# 03_MCU.net
KiCad netlist of a schematic drawn in Altium Designer
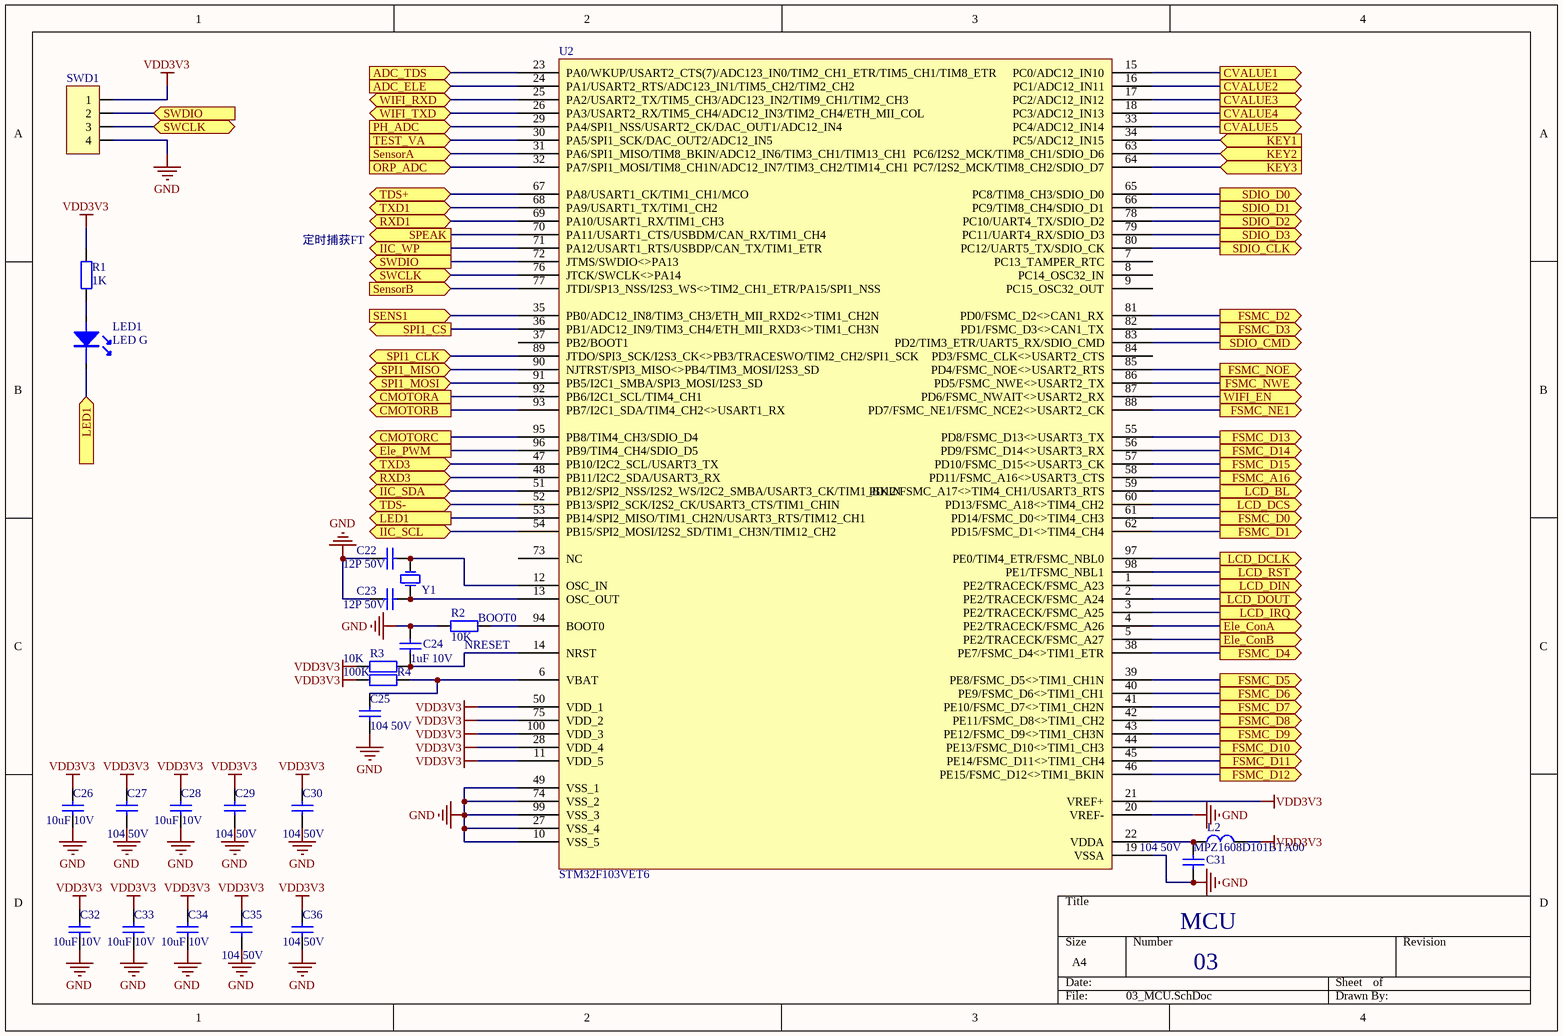
[diagram p0: 03_MCU.SchDoc]

(export (version "E")
  (design (tool "Eeschema 10.0.6"))
  (components
    (comp (ref "C22")
      (value "12P 50V")
      (footprint "SMD-0603C")
      (description "贴片电容 5%")
      (libsource (lib "XiaoyI") (part "CAP4"))
    )
    (comp (ref "C23")
      (value "12P 50V")
      (footprint "SMD-0603C")
      (description "贴片电容 5%")
      (libsource (lib "XiaoyI") (part "CAP4"))
    )
    (comp (ref "C24")
      (value "1uF 10V")
      (footprint "SMD-0603C")
      (description "贴片电容 20%")
      (libsource (lib "XiaoyI") (part "CAP4"))
    )
    (comp (ref "C25")
      (value "104 50V")
      (footprint "SMD-0603C")
      (description "贴片电容 20%")
      (libsource (lib "XiaoyI") (part "CAP4"))
    )
    (comp (ref "C26")
      (value "10uF 10V")
      (footprint "SMD-0603C")
      (description "贴片电容 20%")
      (libsource (lib "XiaoyI") (part "CAP4"))
    )
    (comp (ref "C27")
      (value "104 50V")
      (footprint "SMD-0603C")
      (description "贴片电容 20%")
      (libsource (lib "XiaoyI") (part "CAP4"))
    )
    (comp (ref "C28")
      (value "10uF 10V")
      (footprint "SMD-0603C")
      (description "贴片电容 20%")
      (libsource (lib "XiaoyI") (part "CAP4"))
    )
    (comp (ref "C29")
      (value "104 50V")
      (footprint "SMD-0603C")
      (description "贴片电容 20%")
      (libsource (lib "XiaoyI") (part "CAP4"))
    )
    (comp (ref "C30")
      (value "104 50V")
      (footprint "SMD-0603C")
      (description "贴片电容 20%")
      (libsource (lib "XiaoyI") (part "CAP4"))
    )
    (comp (ref "C31")
      (value "104 50V")
      (footprint "SMD-0603C")
      (description "贴片电容 20%")
      (libsource (lib "XiaoyI") (part "CAP4"))
    )
    (comp (ref "C32")
      (value "10uF 10V")
      (footprint "SMD-0603C")
      (description "贴片电容 20%")
      (libsource (lib "XiaoyI") (part "CAP4"))
    )
    (comp (ref "C33")
      (value "10uF 10V")
      (footprint "SMD-0603C")
      (description "贴片电容 20%")
      (libsource (lib "XiaoyI") (part "CAP4"))
    )
    (comp (ref "C34")
      (value "10uF 10V")
      (footprint "SMD-0603C")
      (description "贴片电容 20%")
      (libsource (lib "XiaoyI") (part "CAP4"))
    )
    (comp (ref "C35")
      (value "104 50V")
      (footprint "SMD-0603C")
      (description "贴片电容 20%")
      (libsource (lib "XiaoyI") (part "CAP4"))
    )
    (comp (ref "C36")
      (value "104 50V")
      (footprint "SMD-0603C")
      (description "贴片电容 20%")
      (libsource (lib "XiaoyI") (part "CAP4"))
    )
    (comp (ref "L2")
      (value "MPZ1608D101BTA00")
      (footprint "SMD-0603")
      (description "磁珠电感 100R 100MHz")
      (libsource (lib "XiaoyI") (part "CIZHU1"))
    )
    (comp (ref "LED1")
      (value "LED G")
      (footprint "SMD-0603D")
      (description "绿色普亮")
      (libsource (lib "ABB") (part "LED"))
    )
    (comp (ref "R1")
      (value "1K")
      (footprint "SMD-0603")
      (description "贴片电阻 5%")
      (libsource (lib "ABB") (part "RES0"))
    )
    (comp (ref "R2")
      (value "10K")
      (footprint "SMD-0603")
      (description "贴片电阻 5%")
      (libsource (lib "XiaoyI") (part "RES2"))
    )
    (comp (ref "R3")
      (value "10K")
      (footprint "SMD-0603")
      (description "贴片电阻 5%")
      (libsource (lib "XiaoyI") (part "RES2"))
    )
    (comp (ref "R4")
      (value "100K")
      (footprint "SMD-0603")
      (description "贴片电阻 5%")
      (libsource (lib "XiaoyI") (part "RES2"))
    )
    (comp (ref "SWD1")
      (value "SIP-4 (NC)")
      (footprint "SIP-4")
      (description "ISP 下载")
      (libsource (lib "XiaoyI") (part "SIP-4"))
    )
    (comp (ref "U2")
      (value "STM32F103VET6")
      (footprint "LQFP-100_14X14X05P")
      (libsource (lib "liujingtao_V1.0") (part "STM32F103VET6"))
    )
    (comp (ref "Y1")
      (value "8MHz")
      (footprint "XTAL-3225-2")
      (description "3225 贴片晶振")
      (libsource (lib "XiaoyI") (part "XTAL"))
    )
  )
  (nets
    (net (code "1") (name "/ADC_ELE") (class "Default")
      (node (ref "U2") (pin "24") (pinfunction "PA1/USART2_RTS/ADC123_IN1/TIM5_CH2/TIM2_CH2_24") (pintype "passive"))
    )
    (net (code "2") (name "/ADC_TDS") (class "Default")
      (node (ref "U2") (pin "23") (pinfunction "PA0/WKUP/USART2_CTS(7)/ADC123_IN0/TIM2_CH1_ETR/TIM5_CH1/TIM8_ETR_23") (pintype "passive"))
    )
    (net (code "3") (name "/CMOTORA") (class "Default")
      (node (ref "U2") (pin "92") (pinfunction "PB6/I2C1_SCL/TIM4_CH1_92") (pintype "passive"))
    )
    (net (code "4") (name "/CMOTORB") (class "Default")
      (node (ref "U2") (pin "93") (pinfunction "PB7/I2C1_SDA/TIM4_CH2<>USART1_RX_93") (pintype "passive"))
    )
    (net (code "5") (name "/CMOTORC") (class "Default")
      (node (ref "U2") (pin "95") (pinfunction "PB8/TIM4_CH3/SDIO_D4_95") (pintype "passive"))
    )
    (net (code "6") (name "/CVALUE1") (class "Default")
      (node (ref "U2") (pin "15") (pinfunction "PC0/ADC12_IN10_15") (pintype "passive"))
    )
    (net (code "7") (name "/CVALUE2") (class "Default")
      (node (ref "U2") (pin "16") (pinfunction "PC1/ADC12_IN11_16") (pintype "passive"))
    )
    (net (code "8") (name "/CVALUE3") (class "Default")
      (node (ref "U2") (pin "17") (pinfunction "PC2/ADC12_IN12_17") (pintype "passive"))
    )
    (net (code "9") (name "/CVALUE4") (class "Default")
      (node (ref "U2") (pin "18") (pinfunction "PC3/ADC12_IN13_18") (pintype "passive"))
    )
    (net (code "10") (name "/CVALUE5") (class "Default")
      (node (ref "U2") (pin "33") (pinfunction "PC4/ADC12_IN14_33") (pintype "passive"))
    )
    (net (code "11") (name "/Ele_ConA") (class "Default")
      (node (ref "U2") (pin "4") (pinfunction "PE2/TRACECK/FSMC_A26_4") (pintype "passive"))
    )
    (net (code "12") (name "/Ele_ConB") (class "Default")
      (node (ref "U2") (pin "5") (pinfunction "PE2/TRACECK/FSMC_A27_5") (pintype "passive"))
    )
    (net (code "13") (name "/Ele_PWM") (class "Default")
      (node (ref "U2") (pin "96") (pinfunction "PB9/TIM4_CH4/SDIO_D5_96") (pintype "passive"))
    )
    (net (code "14") (name "/FSMC_A16") (class "Default")
      (node (ref "U2") (pin "58") (pinfunction "PD11/FSMC_A16<>USART3_CTS_58") (pintype "passive"))
    )
    (net (code "15") (name "/FSMC_D0") (class "Default")
      (node (ref "U2") (pin "61") (pinfunction "PD14/FSMC_D0<>TIM4_CH3_61") (pintype "passive"))
    )
    (net (code "16") (name "/FSMC_D1") (class "Default")
      (node (ref "U2") (pin "62") (pinfunction "PD15/FSMC_D1<>TIM4_CH4_62") (pintype "passive"))
    )
    (net (code "17") (name "/FSMC_D2") (class "Default")
      (node (ref "U2") (pin "81") (pinfunction "PD0/FSMC_D2<>CAN1_RX_81") (pintype "passive"))
    )
    (net (code "18") (name "/FSMC_D3") (class "Default")
      (node (ref "U2") (pin "82") (pinfunction "PD1/FSMC_D3<>CAN1_TX_82") (pintype "passive"))
    )
    (net (code "19") (name "/FSMC_D4") (class "Default")
      (node (ref "U2") (pin "38") (pinfunction "PE7/FSMC_D4<>TIM1_ETR_38") (pintype "passive"))
    )
    (net (code "20") (name "/FSMC_D5") (class "Default")
      (node (ref "U2") (pin "39") (pinfunction "PE8/FSMC_D5<>TIM1_CH1N_39") (pintype "passive"))
    )
    (net (code "21") (name "/FSMC_D6") (class "Default")
      (node (ref "U2") (pin "40") (pinfunction "PE9/FSMC_D6<>TIM1_CH1_40") (pintype "passive"))
    )
    (net (code "22") (name "/FSMC_D7") (class "Default")
      (node (ref "U2") (pin "41") (pinfunction "PE10/FSMC_D7<>TIM1_CH2N_41") (pintype "passive"))
    )
    (net (code "23") (name "/FSMC_D8") (class "Default")
      (node (ref "U2") (pin "42") (pinfunction "PE11/FSMC_D8<>TIM1_CH2_42") (pintype "passive"))
    )
    (net (code "24") (name "/FSMC_D9") (class "Default")
      (node (ref "U2") (pin "43") (pinfunction "PE12/FSMC_D9<>TIM1_CH3N_43") (pintype "passive"))
    )
    (net (code "25") (name "/FSMC_D10") (class "Default")
      (node (ref "U2") (pin "44") (pinfunction "PE13/FSMC_D10<>TIM1_CH3_44") (pintype "passive"))
    )
    (net (code "26") (name "/FSMC_D11") (class "Default")
      (node (ref "U2") (pin "45") (pinfunction "PE14/FSMC_D11<>TIM1_CH4_45") (pintype "passive"))
    )
    (net (code "27") (name "/FSMC_D12") (class "Default")
      (node (ref "U2") (pin "46") (pinfunction "PE15/FSMC_D12<>TIM1_BKIN_46") (pintype "passive"))
    )
    (net (code "28") (name "/FSMC_D13") (class "Default")
      (node (ref "U2") (pin "55") (pinfunction "PD8/FSMC_D13<>USART3_TX_55") (pintype "passive"))
    )
    (net (code "29") (name "/FSMC_D14") (class "Default")
      (node (ref "U2") (pin "56") (pinfunction "PD9/FSMC_D14<>USART3_RX_56") (pintype "passive"))
    )
    (net (code "30") (name "/FSMC_D15") (class "Default")
      (node (ref "U2") (pin "57") (pinfunction "PD10/FSMC_D15<>USART3_CK_57") (pintype "passive"))
    )
    (net (code "31") (name "/FSMC_NE1") (class "Default")
      (node (ref "U2") (pin "88") (pinfunction "PD7/FSMC_NE1/FSMC_NCE2<>USART2_CK_88") (pintype "passive"))
    )
    (net (code "32") (name "/FSMC_NOE") (class "Default")
      (node (ref "U2") (pin "85") (pinfunction "PD4/FSMC_NOE<>USART2_RTS_85") (pintype "passive"))
    )
    (net (code "33") (name "/FSMC_NWE") (class "Default")
      (node (ref "U2") (pin "86") (pinfunction "PD5/FSMC_NWE<>USART2_TX_86") (pintype "passive"))
    )
    (net (code "34") (name "/IIC_SCL") (class "Default")
      (node (ref "U2") (pin "54") (pinfunction "PB15/SPI2_MOSI/I2S2_SD/TIM1_CH3N/TIM12_CH2_54") (pintype "passive"))
    )
    (net (code "35") (name "/IIC_SDA") (class "Default")
      (node (ref "U2") (pin "51") (pinfunction "PB12/SPI2_NSS/I2S2_WS/I2C2_SMBA/USART3_CK/TIM1_BKIN_51") (pintype "passive"))
    )
    (net (code "36") (name "/IIC_WP") (class "Default")
      (node (ref "U2") (pin "71") (pinfunction "PA12/USART1_RTS/USBDP/CAN_TX/TIM1_ETR_71") (pintype "passive"))
    )
    (net (code "37") (name "/KEY1") (class "Default")
      (node (ref "U2") (pin "34") (pinfunction "PC5/ADC12_IN15_34") (pintype "passive"))
    )
    (net (code "38") (name "/KEY2") (class "Default")
      (node (ref "U2") (pin "63") (pinfunction "PC6/I2S2_MCK/TIM8_CH1/SDIO_D6_63") (pintype "passive"))
    )
    (net (code "39") (name "/KEY3") (class "Default")
      (node (ref "U2") (pin "64") (pinfunction "PC7/I2S2_MCK/TIM8_CH2/SDIO_D7_64") (pintype "passive"))
    )
    (net (code "40") (name "/LCD_BL") (class "Default")
      (node (ref "U2") (pin "59") (pinfunction "PD12/FSMC_A17<>TIM4_CH1/USART3_RTS_59") (pintype "passive"))
    )
    (net (code "41") (name "/LCD_DCLK") (class "Default")
      (node (ref "U2") (pin "97") (pinfunction "PE0/TIM4_ETR/FSMC_NBL0_97") (pintype "passive"))
    )
    (net (code "42") (name "/LCD_DCS") (class "Default")
      (node (ref "U2") (pin "60") (pinfunction "PD13/FSMC_A18<>TIM4_CH2_60") (pintype "passive"))
    )
    (net (code "43") (name "/LCD_DIN") (class "Default")
      (node (ref "U2") (pin "1") (pinfunction "PE2/TRACECK/FSMC_A23_1") (pintype "passive"))
    )
    (net (code "44") (name "/LCD_DOUT") (class "Default")
      (node (ref "U2") (pin "2") (pinfunction "PE2/TRACECK/FSMC_A24_2") (pintype "passive"))
    )
    (net (code "45") (name "/LCD_IRQ") (class "Default")
      (node (ref "U2") (pin "3") (pinfunction "PE2/TRACECK/FSMC_A25_3") (pintype "passive"))
    )
    (net (code "46") (name "/LCD_RST") (class "Default")
      (node (ref "U2") (pin "98") (pinfunction "PE1/TFSMC_NBL1_98") (pintype "passive"))
    )
    (net (code "47") (name "/LED1") (class "Default")
      (node (ref "LED1") (pin "2") (pinfunction "K_2") (pintype "passive"))
      (node (ref "U2") (pin "53") (pinfunction "PB14/SPI2_MISO/TIM1_CH2N/USART3_RTS/TIM12_CH1_53") (pintype "passive"))
    )
    (net (code "48") (name "/ORP_ADC") (class "Default")
      (node (ref "U2") (pin "32") (pinfunction "PA7/SPI1_MOSI/TIM8_CH1N/ADC12_IN7/TIM3_CH2/TIM14_CH1_32") (pintype "passive"))
    )
    (net (code "49") (name "/PH_ADC") (class "Default")
      (node (ref "U2") (pin "29") (pinfunction "PA4/SPI1_NSS/USART2_CK/DAC_OUT1/ADC12_IN4_29") (pintype "passive"))
    )
    (net (code "50") (name "/RXD1") (class "Default")
      (node (ref "U2") (pin "69") (pinfunction "PA10/USART1_RX/TIM1_CH3_69") (pintype "passive"))
    )
    (net (code "51") (name "/RXD3") (class "Default")
      (node (ref "U2") (pin "48") (pinfunction "PB11/I2C2_SDA/USART3_RX_48") (pintype "passive"))
    )
    (net (code "52") (name "/SDIO_CLK") (class "Default")
      (node (ref "U2") (pin "80") (pinfunction "PC12/UART5_TX/SDIO_CK_80") (pintype "passive"))
    )
    (net (code "53") (name "/SDIO_CMD") (class "Default")
      (node (ref "U2") (pin "83") (pinfunction "PD2/TIM3_ETR/UART5_RX/SDIO_CMD_83") (pintype "passive"))
    )
    (net (code "54") (name "/SDIO_D0") (class "Default")
      (node (ref "U2") (pin "65") (pinfunction "PC8/TIM8_CH3/SDIO_D0_65") (pintype "passive"))
    )
    (net (code "55") (name "/SDIO_D1") (class "Default")
      (node (ref "U2") (pin "66") (pinfunction "PC9/TIM8_CH4/SDIO_D1_66") (pintype "passive"))
    )
    (net (code "56") (name "/SDIO_D2") (class "Default")
      (node (ref "U2") (pin "78") (pinfunction "PC10/UART4_TX/SDIO_D2_78") (pintype "passive"))
    )
    (net (code "57") (name "/SDIO_D3") (class "Default")
      (node (ref "U2") (pin "79") (pinfunction "PC11/UART4_RX/SDIO_D3_79") (pintype "passive"))
    )
    (net (code "58") (name "/SENS1") (class "Default")
      (node (ref "U2") (pin "35") (pinfunction "PB0/ADC12_IN8/TIM3_CH3/ETH_MII_RXD2<>TIM1_CH2N_35") (pintype "passive"))
    )
    (net (code "59") (name "/SPEAK") (class "Default")
      (node (ref "U2") (pin "70") (pinfunction "PA11/USART1_CTS/USBDM/CAN_RX/TIM1_CH4_70") (pintype "passive"))
    )
    (net (code "60") (name "/SPI1_CLK") (class "Default")
      (node (ref "U2") (pin "89") (pinfunction "JTDO/SPI3_SCK/I2S3_CK<>PB3/TRACESWO/TIM2_CH2/SPI1_SCK_89") (pintype "passive"))
    )
    (net (code "61") (name "/SPI1_CS") (class "Default")
      (node (ref "U2") (pin "36") (pinfunction "PB1/ADC12_IN9/TIM3_CH4/ETH_MII_RXD3<>TIM1_CH3N_36") (pintype "passive"))
    )
    (net (code "62") (name "/SPI1_MISO") (class "Default")
      (node (ref "U2") (pin "90") (pinfunction "NJTRST/SPI3_MISO<>PB4/TIM3_MOSI/I2S3_SD_90") (pintype "passive"))
    )
    (net (code "63") (name "/SPI1_MOSI") (class "Default")
      (node (ref "U2") (pin "91") (pinfunction "PB5/I2C1_SMBA/SPI3_MOSI/I2S3_SD_91") (pintype "passive"))
    )
    (net (code "64") (name "/SWCLK") (class "Default")
      (node (ref "SWD1") (pin "3") (pinfunction "3_3") (pintype "passive"))
      (node (ref "U2") (pin "76") (pinfunction "JTCK/SWCLK<>PA14_76") (pintype "passive"))
    )
    (net (code "65") (name "/SWDIO") (class "Default")
      (node (ref "SWD1") (pin "2") (pinfunction "2_2") (pintype "passive"))
      (node (ref "U2") (pin "72") (pinfunction "JTMS/SWDIO<>PA13_72") (pintype "passive"))
    )
    (net (code "66") (name "/SensorA") (class "Default")
      (node (ref "U2") (pin "31") (pinfunction "PA6/SPI1_MISO/TIM8_BKIN/ADC12_IN6/TIM3_CH1/TIM13_CH1_31") (pintype "passive"))
    )
    (net (code "67") (name "/SensorB") (class "Default")
      (node (ref "U2") (pin "77") (pinfunction "JTDI/SP13_NSS/I2S3_WS<>TIM2_CH1_ETR/PA15/SPI1_NSS_77") (pintype "passive"))
    )
    (net (code "68") (name "/TDS+") (class "Default")
      (node (ref "U2") (pin "67") (pinfunction "PA8/USART1_CK/TIM1_CH1/MCO_67") (pintype "passive"))
    )
    (net (code "69") (name "/TDS-") (class "Default")
      (node (ref "U2") (pin "52") (pinfunction "PB13/SPI2_SCK/I2S2_CK/USART3_CTS/TIM1_CHIN_52") (pintype "passive"))
    )
    (net (code "70") (name "/TEST_VA") (class "Default")
      (node (ref "U2") (pin "30") (pinfunction "PA5/SPI1_SCK/DAC_OUT2/ADC12_IN5_30") (pintype "passive"))
    )
    (net (code "71") (name "/TXD1") (class "Default")
      (node (ref "U2") (pin "68") (pinfunction "PA9/USART1_TX/TIM1_CH2_68") (pintype "passive"))
    )
    (net (code "72") (name "/TXD3") (class "Default")
      (node (ref "U2") (pin "47") (pinfunction "PB10/I2C2_SCL/USART3_TX_47") (pintype "passive"))
    )
    (net (code "73") (name "/WIFI_EN") (class "Default")
      (node (ref "U2") (pin "87") (pinfunction "PD6/FSMC_NWAIT<>USART2_RX_87") (pintype "passive"))
    )
    (net (code "74") (name "/WIFI_RXD") (class "Default")
      (node (ref "U2") (pin "25") (pinfunction "PA2/USART2_TX/TIM5_CH3/ADC123_IN2/TIM9_CH1/TIM2_CH3_25") (pintype "passive"))
    )
    (net (code "75") (name "/WIFI_TXD") (class "Default")
      (node (ref "U2") (pin "26") (pinfunction "PA3/USART2_RX/TIM5_CH4/ADC12_IN3/TIM2_CH4/ETH_MII_COL_26") (pintype "passive"))
    )
    (net (code "76") (name "GND") (class "Default")
      (node (ref "C22") (pin "2") (pinfunction "2_2") (pintype "passive"))
      (node (ref "C23") (pin "2") (pinfunction "2_2") (pintype "passive"))
      (node (ref "C24") (pin "1") (pinfunction "1_1") (pintype "passive"))
      (node (ref "C25") (pin "1") (pinfunction "1_1") (pintype "passive"))
      (node (ref "C26") (pin "1") (pinfunction "1_1") (pintype "passive"))
      (node (ref "C27") (pin "1") (pinfunction "1_1") (pintype "passive"))
      (node (ref "C28") (pin "1") (pinfunction "1_1") (pintype "passive"))
      (node (ref "C29") (pin "1") (pinfunction "1_1") (pintype "passive"))
      (node (ref "C30") (pin "1") (pinfunction "1_1") (pintype "passive"))
      (node (ref "C31") (pin "1") (pinfunction "1_1") (pintype "passive"))
      (node (ref "C32") (pin "1") (pinfunction "1_1") (pintype "passive"))
      (node (ref "C33") (pin "1") (pinfunction "1_1") (pintype "passive"))
      (node (ref "C34") (pin "1") (pinfunction "1_1") (pintype "passive"))
      (node (ref "C35") (pin "1") (pinfunction "1_1") (pintype "passive"))
      (node (ref "C36") (pin "1") (pinfunction "1_1") (pintype "passive"))
      (node (ref "R2") (pin "2") (pinfunction "2_2") (pintype "passive"))
      (node (ref "SWD1") (pin "4") (pinfunction "4_4") (pintype "passive"))
      (node (ref "U2") (pin "10") (pinfunction "VSS_5_10") (pintype "passive"))
      (node (ref "U2") (pin "19") (pinfunction "VSSA_19") (pintype "passive"))
      (node (ref "U2") (pin "20") (pinfunction "VREF-_20") (pintype "passive"))
      (node (ref "U2") (pin "27") (pinfunction "VSS_4_27") (pintype "passive"))
      (node (ref "U2") (pin "49") (pinfunction "VSS_1_49") (pintype "passive"))
      (node (ref "U2") (pin "74") (pinfunction "VSS_2_74") (pintype "passive"))
      (node (ref "U2") (pin "99") (pinfunction "VSS_3_99") (pintype "passive"))
    )
    (net (code "77") (name "Net-(LED1-A)") (class "Default")
      (node (ref "LED1") (pin "1") (pinfunction "A_1") (pintype "passive"))
      (node (ref "R1") (pin "1") (pinfunction "1_1") (pintype "passive"))
    )
    (net (code "78") (name "Net-(U2-BOOT0)") (class "Default")
      (node (ref "R2") (pin "1") (pinfunction "1_1") (pintype "passive"))
      (node (ref "U2") (pin "94") (pinfunction "BOOT0_94") (pintype "passive"))
    )
    (net (code "79") (name "Net-(U2-NRST)") (class "Default")
      (node (ref "C24") (pin "2") (pinfunction "2_2") (pintype "passive"))
      (node (ref "R3") (pin "1") (pinfunction "1_1") (pintype "passive"))
      (node (ref "U2") (pin "14") (pinfunction "NRST_14") (pintype "passive"))
    )
    (net (code "80") (name "Net-(U2-OSC_IN)") (class "Default")
      (node (ref "C22") (pin "1") (pinfunction "1_1") (pintype "passive"))
      (node (ref "U2") (pin "12") (pinfunction "OSC_IN_12") (pintype "passive"))
      (node (ref "Y1") (pin "2") (pinfunction "OSC2_2") (pintype "passive"))
    )
    (net (code "81") (name "Net-(U2-OSC_OUT)") (class "Default")
      (node (ref "C23") (pin "1") (pinfunction "1_1") (pintype "passive"))
      (node (ref "U2") (pin "13") (pinfunction "OSC_OUT_13") (pintype "passive"))
      (node (ref "Y1") (pin "1") (pinfunction "OSC1_1") (pintype "passive"))
    )
    (net (code "82") (name "Net-(U2-VBAT)") (class "Default")
      (node (ref "C25") (pin "2") (pinfunction "2_2") (pintype "passive"))
      (node (ref "R4") (pin "1") (pinfunction "1_1") (pintype "passive"))
      (node (ref "U2") (pin "6") (pinfunction "VBAT_6") (pintype "passive"))
    )
    (net (code "83") (name "Net-(U2-VDDA)") (class "Default")
      (node (ref "C31") (pin "2") (pinfunction "2_2") (pintype "passive"))
      (node (ref "L2") (pin "2") (pinfunction "2_2") (pintype "passive"))
      (node (ref "U2") (pin "22") (pinfunction "VDDA_22") (pintype "passive"))
    )
    (net (code "84") (name "VDD3V3") (class "Default")
      (node (ref "C26") (pin "2") (pinfunction "2_2") (pintype "passive"))
      (node (ref "C27") (pin "2") (pinfunction "2_2") (pintype "passive"))
      (node (ref "C28") (pin "2") (pinfunction "2_2") (pintype "passive"))
      (node (ref "C29") (pin "2") (pinfunction "2_2") (pintype "passive"))
      (node (ref "C30") (pin "2") (pinfunction "2_2") (pintype "passive"))
      (node (ref "C32") (pin "2") (pinfunction "2_2") (pintype "passive"))
      (node (ref "C33") (pin "2") (pinfunction "2_2") (pintype "passive"))
      (node (ref "C34") (pin "2") (pinfunction "2_2") (pintype "passive"))
      (node (ref "C35") (pin "2") (pinfunction "2_2") (pintype "passive"))
      (node (ref "C36") (pin "2") (pinfunction "2_2") (pintype "passive"))
      (node (ref "L2") (pin "1") (pinfunction "1_1") (pintype "passive"))
      (node (ref "R1") (pin "2") (pinfunction "2_2") (pintype "passive"))
      (node (ref "R3") (pin "2") (pinfunction "2_2") (pintype "passive"))
      (node (ref "R4") (pin "2") (pinfunction "2_2") (pintype "passive"))
      (node (ref "SWD1") (pin "1") (pinfunction "1_1") (pintype "passive"))
      (node (ref "U2") (pin "100") (pinfunction "VDD_3_100") (pintype "passive"))
      (node (ref "U2") (pin "11") (pinfunction "VDD_5_11") (pintype "passive"))
      (node (ref "U2") (pin "21") (pinfunction "VREF+_21") (pintype "passive"))
      (node (ref "U2") (pin "28") (pinfunction "VDD_4_28") (pintype "passive"))
      (node (ref "U2") (pin "50") (pinfunction "VDD_1_50") (pintype "passive"))
      (node (ref "U2") (pin "75") (pinfunction "VDD_2_75") (pintype "passive"))
    )
    (net (code "85") (name "unconnected-(U2-NC-Pad73)") (class "Default")
      (node (ref "U2") (pin "73") (pinfunction "NC_73") (pintype "passive"))
    )
    (net (code "86") (name "unconnected-(U2-PB2{slash}BOOT1-Pad37)") (class "Default")
      (node (ref "U2") (pin "37") (pinfunction "PB2/BOOT1_37") (pintype "passive"))
    )
    (net (code "87") (name "unconnected-(U2-PC13_TAMPER_RTC-Pad7)") (class "Default")
      (node (ref "U2") (pin "7") (pinfunction "PC13_TAMPER_RTC_7") (pintype "passive"))
    )
    (net (code "88") (name "unconnected-(U2-PC14_OSC32_IN-Pad8)") (class "Default")
      (node (ref "U2") (pin "8") (pinfunction "PC14_OSC32_IN_8") (pintype "passive"))
    )
    (net (code "89") (name "unconnected-(U2-PC15_OSC32_OUT-Pad9)") (class "Default")
      (node (ref "U2") (pin "9") (pinfunction "PC15_OSC32_OUT_9") (pintype "passive"))
    )
    (net (code "90") (name "unconnected-(U2-PD3{slash}FSMC_CLK<>USART2_CTS-Pad84)") (class "Default")
      (node (ref "U2") (pin "84") (pinfunction "PD3/FSMC_CLK<>USART2_CTS_84") (pintype "passive"))
    )
  )
)
